# BigFace.net
KiCad netlist of a schematic drawn in EAGLE
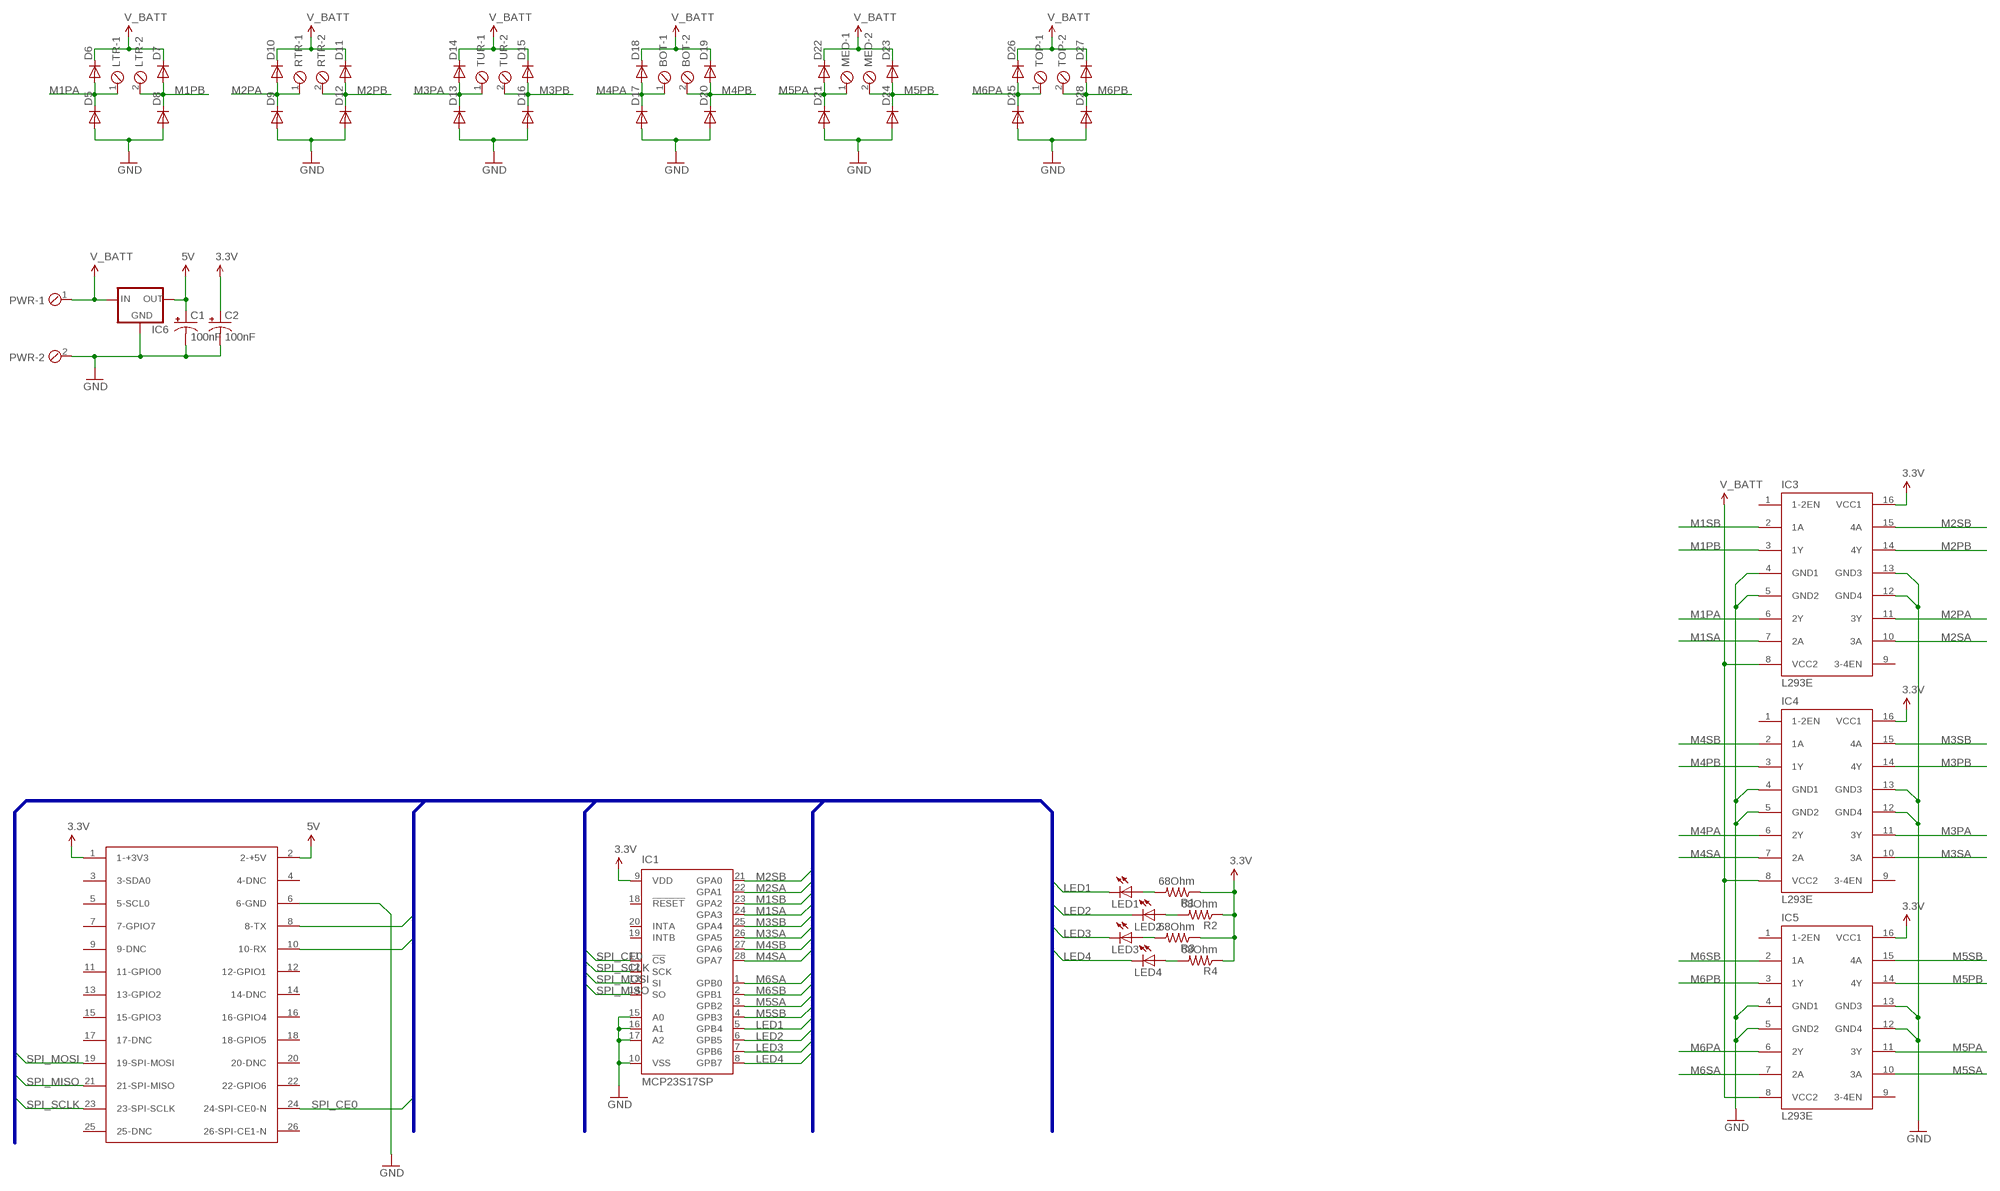
[diagram p0: schematic, sheet 1]

(export (version "E")
  (design (tool "Eeschema 10.0.6"))
  (components
    (comp (ref "BOT")
      (value "MPT2")
      (footprint "eagle-import:2POL254")
      (libsource (lib "eagle-import") (part "MPT2"))
    )
    (comp (ref "C1")
      (value "100nF")
      (footprint "eagle-import:CPOL-RADIAL-10UF-25V")
      (libsource (lib "eagle-import") (part "CAP_POLPTH2"))
    )
    (comp (ref "C2")
      (value "100nF")
      (footprint "eagle-import:CPOL-RADIAL-10UF-25V")
      (libsource (lib "eagle-import") (part "CAP_POLPTH2"))
    )
    (comp (ref "D5")
      (value "DIODE1N4148")
      (footprint "eagle-import:DIODE-1N4148")
      (libsource (lib "eagle-import") (part "DIODE1N4148"))
    )
    (comp (ref "D6")
      (value "DIODE1N4148")
      (footprint "eagle-import:DIODE-1N4148")
      (libsource (lib "eagle-import") (part "DIODE1N4148"))
    )
    (comp (ref "D7")
      (value "DIODE1N4148")
      (footprint "eagle-import:DIODE-1N4148")
      (libsource (lib "eagle-import") (part "DIODE1N4148"))
    )
    (comp (ref "D8")
      (value "DIODE1N4148")
      (footprint "eagle-import:DIODE-1N4148")
      (libsource (lib "eagle-import") (part "DIODE1N4148"))
    )
    (comp (ref "D9")
      (value "DIODE1N4148")
      (footprint "eagle-import:DIODE-1N4148")
      (libsource (lib "eagle-import") (part "DIODE1N4148"))
    )
    (comp (ref "D10")
      (value "DIODE1N4148")
      (footprint "eagle-import:DIODE-1N4148")
      (libsource (lib "eagle-import") (part "DIODE1N4148"))
    )
    (comp (ref "D11")
      (value "DIODE1N4148")
      (footprint "eagle-import:DIODE-1N4148")
      (libsource (lib "eagle-import") (part "DIODE1N4148"))
    )
    (comp (ref "D12")
      (value "DIODE1N4148")
      (footprint "eagle-import:DIODE-1N4148")
      (libsource (lib "eagle-import") (part "DIODE1N4148"))
    )
    (comp (ref "D13")
      (value "DIODE1N4148")
      (footprint "eagle-import:DIODE-1N4148")
      (libsource (lib "eagle-import") (part "DIODE1N4148"))
    )
    (comp (ref "D14")
      (value "DIODE1N4148")
      (footprint "eagle-import:DIODE-1N4148")
      (libsource (lib "eagle-import") (part "DIODE1N4148"))
    )
    (comp (ref "D15")
      (value "DIODE1N4148")
      (footprint "eagle-import:DIODE-1N4148")
      (libsource (lib "eagle-import") (part "DIODE1N4148"))
    )
    (comp (ref "D16")
      (value "DIODE1N4148")
      (footprint "eagle-import:DIODE-1N4148")
      (libsource (lib "eagle-import") (part "DIODE1N4148"))
    )
    (comp (ref "D17")
      (value "DIODE1N4148")
      (footprint "eagle-import:DIODE-1N4148")
      (libsource (lib "eagle-import") (part "DIODE1N4148"))
    )
    (comp (ref "D18")
      (value "DIODE1N4148")
      (footprint "eagle-import:DIODE-1N4148")
      (libsource (lib "eagle-import") (part "DIODE1N4148"))
    )
    (comp (ref "D19")
      (value "DIODE1N4148")
      (footprint "eagle-import:DIODE-1N4148")
      (libsource (lib "eagle-import") (part "DIODE1N4148"))
    )
    (comp (ref "D20")
      (value "DIODE1N4148")
      (footprint "eagle-import:DIODE-1N4148")
      (libsource (lib "eagle-import") (part "DIODE1N4148"))
    )
    (comp (ref "D21")
      (value "DIODE1N4148")
      (footprint "eagle-import:DIODE-1N4148")
      (libsource (lib "eagle-import") (part "DIODE1N4148"))
    )
    (comp (ref "D22")
      (value "DIODE1N4148")
      (footprint "eagle-import:DIODE-1N4148")
      (libsource (lib "eagle-import") (part "DIODE1N4148"))
    )
    (comp (ref "D23")
      (value "DIODE1N4148")
      (footprint "eagle-import:DIODE-1N4148")
      (libsource (lib "eagle-import") (part "DIODE1N4148"))
    )
    (comp (ref "D24")
      (value "DIODE1N4148")
      (footprint "eagle-import:DIODE-1N4148")
      (libsource (lib "eagle-import") (part "DIODE1N4148"))
    )
    (comp (ref "D25")
      (value "DIODE1N4148")
      (footprint "eagle-import:DIODE-1N4148")
      (libsource (lib "eagle-import") (part "DIODE1N4148"))
    )
    (comp (ref "D26")
      (value "DIODE1N4148")
      (footprint "eagle-import:DIODE-1N4148")
      (libsource (lib "eagle-import") (part "DIODE1N4148"))
    )
    (comp (ref "D27")
      (value "DIODE1N4148")
      (footprint "eagle-import:DIODE-1N4148")
      (libsource (lib "eagle-import") (part "DIODE1N4148"))
    )
    (comp (ref "D28")
      (value "DIODE1N4148")
      (footprint "eagle-import:DIODE-1N4148")
      (libsource (lib "eagle-import") (part "DIODE1N4148"))
    )
    (comp (ref "IC1")
      (value "MCP23S17SP")
      (footprint "eagle-import:DIL28-3")
      (fields (field (name "MF") "MICROCHIP") (field (name "MPN") "MCP23S17-E/SP"))
      (libsource (lib "eagle-import") (part "MCP23S17SP"))
    )
    (comp (ref "IC3")
      (value "L293E")
      (footprint "eagle-import:DIL16")
      (fields (field (name "MF") "Arrow Electronics"))
      (libsource (lib "eagle-import") (part "L293E"))
    )
    (comp (ref "IC4")
      (value "L293E")
      (footprint "eagle-import:DIL16")
      (fields (field (name "MF") "Arrow Electronics"))
      (libsource (lib "eagle-import") (part "L293E"))
    )
    (comp (ref "IC5")
      (value "L293E")
      (footprint "eagle-import:DIL16")
      (fields (field (name "MF") "Arrow Electronics"))
      (libsource (lib "eagle-import") (part "L293E"))
    )
    (comp (ref "IC6")
      (value "V_REG_78XXSINK")
      (footprint "eagle-import:TO220-IGO")
      (libsource (lib "eagle-import") (part "V_REG_78XXSINK"))
    )
    (comp (ref "LED1")
      (value "LED3MM")
      (footprint "eagle-import:LED3MM")
      (libsource (lib "eagle-import") (part "LED3MM"))
    )
    (comp (ref "LED2")
      (value "LED3MM")
      (footprint "eagle-import:LED3MM")
      (libsource (lib "eagle-import") (part "LED3MM"))
    )
    (comp (ref "LED3")
      (value "LED3MM")
      (footprint "eagle-import:LED3MM")
      (libsource (lib "eagle-import") (part "LED3MM"))
    )
    (comp (ref "LED4")
      (value "LED3MM")
      (footprint "eagle-import:LED3MM")
      (libsource (lib "eagle-import") (part "LED3MM"))
    )
    (comp (ref "LTR")
      (value "MPT2")
      (footprint "eagle-import:2POL254")
      (libsource (lib "eagle-import") (part "MPT2"))
    )
    (comp (ref "MED")
      (value "MPT2")
      (footprint "eagle-import:2POL254")
      (libsource (lib "eagle-import") (part "MPT2"))
    )
    (comp (ref "PWR")
      (value "MPT2")
      (footprint "eagle-import:2POL254")
      (libsource (lib "eagle-import") (part "MPT2"))
    )
    (comp (ref "R1")
      (value "68Ohm")
      (footprint "eagle-import:AXIAL-0.3EZ")
      (libsource (lib "eagle-import") (part "RESISTOREZ"))
    )
    (comp (ref "R2")
      (value "68Ohm")
      (footprint "eagle-import:AXIAL-0.3EZ")
      (libsource (lib "eagle-import") (part "RESISTOREZ"))
    )
    (comp (ref "R3")
      (value "68Ohm")
      (footprint "eagle-import:AXIAL-0.3EZ")
      (libsource (lib "eagle-import") (part "RESISTOREZ"))
    )
    (comp (ref "R4")
      (value "68Ohm")
      (footprint "eagle-import:AXIAL-0.3EZ")
      (libsource (lib "eagle-import") (part "RESISTOREZ"))
    )
    (comp (ref "RTR")
      (value "MPT2")
      (footprint "eagle-import:2POL254")
      (libsource (lib "eagle-import") (part "MPT2"))
    )
    (comp (ref "TOP")
      (value "MPT2")
      (footprint "eagle-import:2POL254")
      (libsource (lib "eagle-import") (part "MPT2"))
    )
    (comp (ref "TUR")
      (value "MPT2")
      (footprint "eagle-import:2POL254")
      (libsource (lib "eagle-import") (part "MPT2"))
    )
    (comp (ref "U$1")
      (value "RASPBERRY-PI")
      (footprint "eagle-import:RASPBERRY-PI")
      (libsource (lib "eagle-import") (part "RASPBERRY-PI"))
    )
  )
  (nets
    (net (code "1") (name "/LED1") (class "Default")
      (node (ref "IC1") (pin "5") (pinfunction "GPB4_5") (pintype "bidirectional"))
      (node (ref "LED1") (pin "K") (pinfunction "C_K") (pintype "passive"))
    )
    (net (code "2") (name "/LED2") (class "Default")
      (node (ref "IC1") (pin "6") (pinfunction "GPB5_6") (pintype "bidirectional"))
      (node (ref "LED2") (pin "K") (pinfunction "C_K") (pintype "passive"))
    )
    (net (code "3") (name "/LED3") (class "Default")
      (node (ref "IC1") (pin "7") (pinfunction "GPB6_7") (pintype "bidirectional"))
      (node (ref "LED3") (pin "K") (pinfunction "C_K") (pintype "passive"))
    )
    (net (code "4") (name "/LED4") (class "Default")
      (node (ref "IC1") (pin "8") (pinfunction "GPB7_8") (pintype "bidirectional"))
      (node (ref "LED4") (pin "K") (pinfunction "C_K") (pintype "passive"))
    )
    (net (code "5") (name "/M1PA") (class "Default")
      (node (ref "D5") (pin "C") (pinfunction "C_C") (pintype "passive"))
      (node (ref "D6") (pin "A") (pinfunction "A_A") (pintype "passive"))
      (node (ref "IC3") (pin "6") (pinfunction "2Y_6") (pintype "output"))
      (node (ref "LTR") (pin "1") (pinfunction "1_1") (pintype "passive"))
    )
    (net (code "6") (name "/M1PB") (class "Default")
      (node (ref "D7") (pin "A") (pinfunction "A_A") (pintype "passive"))
      (node (ref "D8") (pin "C") (pinfunction "C_C") (pintype "passive"))
      (node (ref "IC3") (pin "3") (pinfunction "1Y_3") (pintype "output"))
      (node (ref "LTR") (pin "2") (pinfunction "1_2") (pintype "passive"))
    )
    (net (code "7") (name "/M1SA") (class "Default")
      (node (ref "IC1") (pin "24") (pinfunction "GPA3_24") (pintype "bidirectional"))
      (node (ref "IC3") (pin "7") (pinfunction "2A_7") (pintype "input"))
    )
    (net (code "8") (name "/M1SB") (class "Default")
      (node (ref "IC1") (pin "23") (pinfunction "GPA2_23") (pintype "bidirectional"))
      (node (ref "IC3") (pin "2") (pinfunction "1A_2") (pintype "input"))
    )
    (net (code "9") (name "/M2PA") (class "Default")
      (node (ref "D10") (pin "A") (pinfunction "A_A") (pintype "passive"))
      (node (ref "D9") (pin "C") (pinfunction "C_C") (pintype "passive"))
      (node (ref "IC3") (pin "11") (pinfunction "3Y_11") (pintype "output"))
      (node (ref "RTR") (pin "1") (pinfunction "1_1") (pintype "passive"))
    )
    (net (code "10") (name "/M2PB") (class "Default")
      (node (ref "D11") (pin "A") (pinfunction "A_A") (pintype "passive"))
      (node (ref "D12") (pin "C") (pinfunction "C_C") (pintype "passive"))
      (node (ref "IC3") (pin "14") (pinfunction "4Y_14") (pintype "output"))
      (node (ref "RTR") (pin "2") (pinfunction "1_2") (pintype "passive"))
    )
    (net (code "11") (name "/M2SA") (class "Default")
      (node (ref "IC1") (pin "22") (pinfunction "GPA1_22") (pintype "bidirectional"))
      (node (ref "IC3") (pin "10") (pinfunction "3A_10") (pintype "input"))
    )
    (net (code "12") (name "/M2SB") (class "Default")
      (node (ref "IC1") (pin "21") (pinfunction "GPA0_21") (pintype "bidirectional"))
      (node (ref "IC3") (pin "15") (pinfunction "4A_15") (pintype "input"))
    )
    (net (code "13") (name "/M3PA") (class "Default")
      (node (ref "D13") (pin "C") (pinfunction "C_C") (pintype "passive"))
      (node (ref "D14") (pin "A") (pinfunction "A_A") (pintype "passive"))
      (node (ref "IC4") (pin "11") (pinfunction "3Y_11") (pintype "output"))
      (node (ref "TUR") (pin "1") (pinfunction "1_1") (pintype "passive"))
    )
    (net (code "14") (name "/M3PB") (class "Default")
      (node (ref "D15") (pin "A") (pinfunction "A_A") (pintype "passive"))
      (node (ref "D16") (pin "C") (pinfunction "C_C") (pintype "passive"))
      (node (ref "IC4") (pin "14") (pinfunction "4Y_14") (pintype "output"))
      (node (ref "TUR") (pin "2") (pinfunction "1_2") (pintype "passive"))
    )
    (net (code "15") (name "/M3SA") (class "Default")
      (node (ref "IC1") (pin "26") (pinfunction "GPA5_26") (pintype "bidirectional"))
      (node (ref "IC4") (pin "10") (pinfunction "3A_10") (pintype "input"))
    )
    (net (code "16") (name "/M3SB") (class "Default")
      (node (ref "IC1") (pin "25") (pinfunction "GPA4_25") (pintype "bidirectional"))
      (node (ref "IC4") (pin "15") (pinfunction "4A_15") (pintype "input"))
    )
    (net (code "17") (name "/M4PA") (class "Default")
      (node (ref "BOT") (pin "1") (pinfunction "1_1") (pintype "passive"))
      (node (ref "D17") (pin "C") (pinfunction "C_C") (pintype "passive"))
      (node (ref "D18") (pin "A") (pinfunction "A_A") (pintype "passive"))
      (node (ref "IC4") (pin "6") (pinfunction "2Y_6") (pintype "output"))
    )
    (net (code "18") (name "/M4PB") (class "Default")
      (node (ref "BOT") (pin "2") (pinfunction "1_2") (pintype "passive"))
      (node (ref "D19") (pin "A") (pinfunction "A_A") (pintype "passive"))
      (node (ref "D20") (pin "C") (pinfunction "C_C") (pintype "passive"))
      (node (ref "IC4") (pin "3") (pinfunction "1Y_3") (pintype "output"))
    )
    (net (code "19") (name "/M4SA") (class "Default")
      (node (ref "IC1") (pin "28") (pinfunction "GPA7_28") (pintype "bidirectional"))
      (node (ref "IC4") (pin "7") (pinfunction "2A_7") (pintype "input"))
    )
    (net (code "20") (name "/M4SB") (class "Default")
      (node (ref "IC1") (pin "27") (pinfunction "GPA6_27") (pintype "bidirectional"))
      (node (ref "IC4") (pin "2") (pinfunction "1A_2") (pintype "input"))
    )
    (net (code "21") (name "/M5PA") (class "Default")
      (node (ref "D21") (pin "C") (pinfunction "C_C") (pintype "passive"))
      (node (ref "D22") (pin "A") (pinfunction "A_A") (pintype "passive"))
      (node (ref "IC5") (pin "11") (pinfunction "3Y_11") (pintype "output"))
      (node (ref "MED") (pin "1") (pinfunction "1_1") (pintype "passive"))
    )
    (net (code "22") (name "/M5PB") (class "Default")
      (node (ref "D23") (pin "A") (pinfunction "A_A") (pintype "passive"))
      (node (ref "D24") (pin "C") (pinfunction "C_C") (pintype "passive"))
      (node (ref "IC5") (pin "14") (pinfunction "4Y_14") (pintype "output"))
      (node (ref "MED") (pin "2") (pinfunction "1_2") (pintype "passive"))
    )
    (net (code "23") (name "/M5SA") (class "Default")
      (node (ref "IC1") (pin "3") (pinfunction "GPB2_3") (pintype "bidirectional"))
      (node (ref "IC5") (pin "10") (pinfunction "3A_10") (pintype "input"))
    )
    (net (code "24") (name "/M5SB") (class "Default")
      (node (ref "IC1") (pin "4") (pinfunction "GPB3_4") (pintype "bidirectional"))
      (node (ref "IC5") (pin "15") (pinfunction "4A_15") (pintype "input"))
    )
    (net (code "25") (name "/M6PA") (class "Default")
      (node (ref "D25") (pin "C") (pinfunction "C_C") (pintype "passive"))
      (node (ref "D26") (pin "A") (pinfunction "A_A") (pintype "passive"))
      (node (ref "IC5") (pin "6") (pinfunction "2Y_6") (pintype "output"))
      (node (ref "TOP") (pin "1") (pinfunction "1_1") (pintype "passive"))
    )
    (net (code "26") (name "/M6PB") (class "Default")
      (node (ref "D27") (pin "A") (pinfunction "A_A") (pintype "passive"))
      (node (ref "D28") (pin "C") (pinfunction "C_C") (pintype "passive"))
      (node (ref "IC5") (pin "3") (pinfunction "1Y_3") (pintype "output"))
      (node (ref "TOP") (pin "2") (pinfunction "1_2") (pintype "passive"))
    )
    (net (code "27") (name "/M6SA") (class "Default")
      (node (ref "IC1") (pin "1") (pinfunction "GPB0_1") (pintype "bidirectional"))
      (node (ref "IC5") (pin "7") (pinfunction "2A_7") (pintype "input"))
    )
    (net (code "28") (name "/M6SB") (class "Default")
      (node (ref "IC1") (pin "2") (pinfunction "GPB1_2") (pintype "bidirectional"))
      (node (ref "IC5") (pin "2") (pinfunction "1A_2") (pintype "input"))
    )
    (net (code "29") (name "/SPI_CE0") (class "Default")
      (node (ref "IC1") (pin "11") (pinfunction "~{CS}_11") (pintype "input"))
      (node (ref "U$1") (pin "24") (pinfunction "24-SPI-CE0-N_24") (pintype "bidirectional"))
    )
    (net (code "30") (name "/SPI_MISO") (class "Default")
      (node (ref "IC1") (pin "14") (pinfunction "SO_14") (pintype "output"))
      (node (ref "U$1") (pin "21") (pinfunction "21-SPI-MISO_21") (pintype "bidirectional"))
    )
    (net (code "31") (name "/SPI_MOSI") (class "Default")
      (node (ref "IC1") (pin "13") (pinfunction "SI_13") (pintype "input"))
      (node (ref "U$1") (pin "19") (pinfunction "19-SPI-MOSI_19") (pintype "bidirectional"))
    )
    (net (code "32") (name "/SPI_SCLK") (class "Default")
      (node (ref "IC1") (pin "12") (pinfunction "SCK_12") (pintype "input"))
      (node (ref "U$1") (pin "23") (pinfunction "23-SPI-SCLK_23") (pintype "bidirectional"))
    )
    (net (code "33") (name "3.3V") (class "Default")
      (node (ref "C2") (pin "1") (pinfunction "+_1") (pintype "passive"))
      (node (ref "IC1") (pin "9") (pinfunction "VDD_9") (pintype "power_in"))
      (node (ref "IC3") (pin "16") (pinfunction "VCC1_16") (pintype "power_in"))
      (node (ref "IC4") (pin "16") (pinfunction "VCC1_16") (pintype "power_in"))
      (node (ref "IC5") (pin "16") (pinfunction "VCC1_16") (pintype "power_in"))
      (node (ref "R1") (pin "P$1") (pinfunction "1_P$1") (pintype "passive"))
      (node (ref "R2") (pin "P$1") (pinfunction "1_P$1") (pintype "passive"))
      (node (ref "R3") (pin "P$1") (pinfunction "1_P$1") (pintype "passive"))
      (node (ref "R4") (pin "P$1") (pinfunction "1_P$1") (pintype "passive"))
      (node (ref "U$1") (pin "1") (pinfunction "1-+3V3_1") (pintype "bidirectional"))
    )
    (net (code "34") (name "5V") (class "Default")
      (node (ref "C1") (pin "1") (pinfunction "+_1") (pintype "passive"))
      (node (ref "IC6") (pin "OUT") (pinfunction "OUT_OUT") (pintype "output"))
      (node (ref "U$1") (pin "2") (pinfunction "2-+5V_2") (pintype "bidirectional"))
    )
    (net (code "35") (name "GND") (class "Default")
      (node (ref "C1") (pin "2") (pinfunction "-_2") (pintype "passive"))
      (node (ref "C2") (pin "2") (pinfunction "-_2") (pintype "passive"))
      (node (ref "D12") (pin "A") (pinfunction "A_A") (pintype "passive"))
      (node (ref "D13") (pin "A") (pinfunction "A_A") (pintype "passive"))
      (node (ref "D16") (pin "A") (pinfunction "A_A") (pintype "passive"))
      (node (ref "D17") (pin "A") (pinfunction "A_A") (pintype "passive"))
      (node (ref "D20") (pin "A") (pinfunction "A_A") (pintype "passive"))
      (node (ref "D21") (pin "A") (pinfunction "A_A") (pintype "passive"))
      (node (ref "D24") (pin "A") (pinfunction "A_A") (pintype "passive"))
      (node (ref "D25") (pin "A") (pinfunction "A_A") (pintype "passive"))
      (node (ref "D28") (pin "A") (pinfunction "A_A") (pintype "passive"))
      (node (ref "D5") (pin "A") (pinfunction "A_A") (pintype "passive"))
      (node (ref "D8") (pin "A") (pinfunction "A_A") (pintype "passive"))
      (node (ref "D9") (pin "A") (pinfunction "A_A") (pintype "passive"))
      (node (ref "IC1") (pin "10") (pinfunction "VSS_10") (pintype "power_in"))
      (node (ref "IC1") (pin "15") (pinfunction "A0_15") (pintype "input"))
      (node (ref "IC1") (pin "16") (pinfunction "A1_16") (pintype "input"))
      (node (ref "IC1") (pin "17") (pinfunction "A2_17") (pintype "input"))
      (node (ref "IC3") (pin "12") (pinfunction "GND4_12") (pintype "power_in"))
      (node (ref "IC3") (pin "13") (pinfunction "GND3_13") (pintype "power_in"))
      (node (ref "IC3") (pin "4") (pinfunction "GND1_4") (pintype "power_in"))
      (node (ref "IC3") (pin "5") (pinfunction "GND2_5") (pintype "power_in"))
      (node (ref "IC4") (pin "12") (pinfunction "GND4_12") (pintype "power_in"))
      (node (ref "IC4") (pin "13") (pinfunction "GND3_13") (pintype "power_in"))
      (node (ref "IC4") (pin "4") (pinfunction "GND1_4") (pintype "power_in"))
      (node (ref "IC4") (pin "5") (pinfunction "GND2_5") (pintype "power_in"))
      (node (ref "IC5") (pin "12") (pinfunction "GND4_12") (pintype "power_in"))
      (node (ref "IC5") (pin "13") (pinfunction "GND3_13") (pintype "power_in"))
      (node (ref "IC5") (pin "4") (pinfunction "GND1_4") (pintype "power_in"))
      (node (ref "IC5") (pin "5") (pinfunction "GND2_5") (pintype "power_in"))
      (node (ref "IC6") (pin "GND") (pinfunction "GND_GND") (pintype "input"))
      (node (ref "PWR") (pin "2") (pinfunction "1_2") (pintype "passive"))
      (node (ref "U$1") (pin "6") (pinfunction "6-GND_6") (pintype "bidirectional"))
    )
    (net (code "36") (name "Net-(R1-2)") (class "Default")
      (node (ref "LED1") (pin "A") (pinfunction "A_A") (pintype "passive"))
      (node (ref "R1") (pin "P$2") (pinfunction "2_P$2") (pintype "passive"))
    )
    (net (code "37") (name "Net-(R2-2)") (class "Default")
      (node (ref "LED2") (pin "A") (pinfunction "A_A") (pintype "passive"))
      (node (ref "R2") (pin "P$2") (pinfunction "2_P$2") (pintype "passive"))
    )
    (net (code "38") (name "Net-(R3-2)") (class "Default")
      (node (ref "LED3") (pin "A") (pinfunction "A_A") (pintype "passive"))
      (node (ref "R3") (pin "P$2") (pinfunction "2_P$2") (pintype "passive"))
    )
    (net (code "39") (name "Net-(R4-2)") (class "Default")
      (node (ref "LED4") (pin "A") (pinfunction "A_A") (pintype "passive"))
      (node (ref "R4") (pin "P$2") (pinfunction "2_P$2") (pintype "passive"))
    )
    (net (code "40") (name "V_BATT") (class "Default")
      (node (ref "D10") (pin "C") (pinfunction "C_C") (pintype "passive"))
      (node (ref "D11") (pin "C") (pinfunction "C_C") (pintype "passive"))
      (node (ref "D14") (pin "C") (pinfunction "C_C") (pintype "passive"))
      (node (ref "D15") (pin "C") (pinfunction "C_C") (pintype "passive"))
      (node (ref "D18") (pin "C") (pinfunction "C_C") (pintype "passive"))
      (node (ref "D19") (pin "C") (pinfunction "C_C") (pintype "passive"))
      (node (ref "D22") (pin "C") (pinfunction "C_C") (pintype "passive"))
      (node (ref "D23") (pin "C") (pinfunction "C_C") (pintype "passive"))
      (node (ref "D26") (pin "C") (pinfunction "C_C") (pintype "passive"))
      (node (ref "D27") (pin "C") (pinfunction "C_C") (pintype "passive"))
      (node (ref "D6") (pin "C") (pinfunction "C_C") (pintype "passive"))
      (node (ref "D7") (pin "C") (pinfunction "C_C") (pintype "passive"))
      (node (ref "IC3") (pin "8") (pinfunction "VCC2_8") (pintype "power_in"))
      (node (ref "IC4") (pin "8") (pinfunction "VCC2_8") (pintype "power_in"))
      (node (ref "IC5") (pin "8") (pinfunction "VCC2_8") (pintype "power_in"))
      (node (ref "IC6") (pin "IN") (pinfunction "IN_IN") (pintype "input"))
      (node (ref "PWR") (pin "1") (pinfunction "1_1") (pintype "passive"))
    )
    (net (code "41") (name "unconnected-(IC1-INTA-Pad20)") (class "Default")
      (node (ref "IC1") (pin "20") (pinfunction "INTA_20") (pintype "output"))
    )
    (net (code "42") (name "unconnected-(IC1-INTB-Pad19)") (class "Default")
      (node (ref "IC1") (pin "19") (pinfunction "INTB_19") (pintype "output"))
    )
    (net (code "43") (name "unconnected-(IC1-~{RESET}-Pad18)") (class "Default")
      (node (ref "IC1") (pin "18") (pinfunction "~{RESET}_18") (pintype "input"))
    )
    (net (code "44") (name "unconnected-(IC3-1-2EN-Pad1)") (class "Default")
      (node (ref "IC3") (pin "1") (pinfunction "1-2EN_1") (pintype "input"))
    )
    (net (code "45") (name "unconnected-(IC3-3-4EN-Pad9)") (class "Default")
      (node (ref "IC3") (pin "9") (pinfunction "3-4EN_9") (pintype "input"))
    )
    (net (code "46") (name "unconnected-(IC4-1-2EN-Pad1)") (class "Default")
      (node (ref "IC4") (pin "1") (pinfunction "1-2EN_1") (pintype "input"))
    )
    (net (code "47") (name "unconnected-(IC4-3-4EN-Pad9)") (class "Default")
      (node (ref "IC4") (pin "9") (pinfunction "3-4EN_9") (pintype "input"))
    )
    (net (code "48") (name "unconnected-(IC5-1-2EN-Pad1)") (class "Default")
      (node (ref "IC5") (pin "1") (pinfunction "1-2EN_1") (pintype "input"))
    )
    (net (code "49") (name "unconnected-(IC5-3-4EN-Pad9)") (class "Default")
      (node (ref "IC5") (pin "9") (pinfunction "3-4EN_9") (pintype "input"))
    )
    (net (code "50") (name "unconnected-(U$1-3-SDA0-Pad3)") (class "Default")
      (node (ref "U$1") (pin "3") (pinfunction "3-SDA0_3") (pintype "bidirectional"))
    )
    (net (code "51") (name "unconnected-(U$1-4-DNC-Pad4)") (class "Default")
      (node (ref "U$1") (pin "4") (pinfunction "4-DNC_4") (pintype "bidirectional"))
    )
    (net (code "52") (name "unconnected-(U$1-5-SCL0-Pad5)") (class "Default")
      (node (ref "U$1") (pin "5") (pinfunction "5-SCL0_5") (pintype "bidirectional"))
    )
    (net (code "53") (name "unconnected-(U$1-7-GPIO7-Pad7)") (class "Default")
      (node (ref "U$1") (pin "7") (pinfunction "7-GPIO7_7") (pintype "bidirectional"))
    )
    (net (code "54") (name "unconnected-(U$1-8-TX-Pad8)") (class "Default")
      (node (ref "U$1") (pin "8") (pinfunction "8-TX_8") (pintype "bidirectional"))
    )
    (net (code "55") (name "unconnected-(U$1-9-DNC-Pad9)") (class "Default")
      (node (ref "U$1") (pin "9") (pinfunction "9-DNC_9") (pintype "bidirectional"))
    )
    (net (code "56") (name "unconnected-(U$1-10-RX-Pad10)") (class "Default")
      (node (ref "U$1") (pin "10") (pinfunction "10-RX_10") (pintype "bidirectional"))
    )
    (net (code "57") (name "unconnected-(U$1-11-GPIO0-Pad11)") (class "Default")
      (node (ref "U$1") (pin "11") (pinfunction "11-GPIO0_11") (pintype "bidirectional"))
    )
    (net (code "58") (name "unconnected-(U$1-12-GPIO1-Pad12)") (class "Default")
      (node (ref "U$1") (pin "12") (pinfunction "12-GPIO1_12") (pintype "bidirectional"))
    )
    (net (code "59") (name "unconnected-(U$1-13-GPIO2-Pad13)") (class "Default")
      (node (ref "U$1") (pin "13") (pinfunction "13-GPIO2_13") (pintype "bidirectional"))
    )
    (net (code "60") (name "unconnected-(U$1-14-DNC-Pad14)") (class "Default")
      (node (ref "U$1") (pin "14") (pinfunction "14-DNC_14") (pintype "bidirectional"))
    )
    (net (code "61") (name "unconnected-(U$1-15-GPIO3-Pad15)") (class "Default")
      (node (ref "U$1") (pin "15") (pinfunction "15-GPIO3_15") (pintype "bidirectional"))
    )
    (net (code "62") (name "unconnected-(U$1-16-GPIO4-Pad16)") (class "Default")
      (node (ref "U$1") (pin "16") (pinfunction "16-GPIO4_16") (pintype "bidirectional"))
    )
    (net (code "63") (name "unconnected-(U$1-17-DNC-Pad17)") (class "Default")
      (node (ref "U$1") (pin "17") (pinfunction "17-DNC_17") (pintype "bidirectional"))
    )
    (net (code "64") (name "unconnected-(U$1-18-GPIO5-Pad18)") (class "Default")
      (node (ref "U$1") (pin "18") (pinfunction "18-GPIO5_18") (pintype "bidirectional"))
    )
    (net (code "65") (name "unconnected-(U$1-20-DNC-Pad20)") (class "Default")
      (node (ref "U$1") (pin "20") (pinfunction "20-DNC_20") (pintype "bidirectional"))
    )
    (net (code "66") (name "unconnected-(U$1-22-GPIO6-Pad22)") (class "Default")
      (node (ref "U$1") (pin "22") (pinfunction "22-GPIO6_22") (pintype "bidirectional"))
    )
    (net (code "67") (name "unconnected-(U$1-25-DNC-Pad25)") (class "Default")
      (node (ref "U$1") (pin "25") (pinfunction "25-DNC_25") (pintype "bidirectional"))
    )
    (net (code "68") (name "unconnected-(U$1-26-SPI-CE1-N-Pad26)") (class "Default")
      (node (ref "U$1") (pin "26") (pinfunction "26-SPI-CE1-N_26") (pintype "bidirectional"))
    )
  )
)
